# SHT4x_2.net
KiCad netlist of a schematic drawn in EAGLE
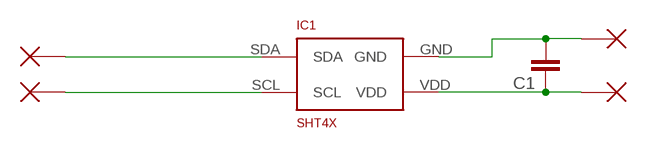
[diagram p0: schematic, sheet 1]

(export (version "E")
  (design (tool "Eeschema 10.0.6"))
  (components
    (comp (ref "C1")
      (value "SMD-C-1206")
      (footprint "eagle-import:C1206")
      (libsource (lib "eagle-import") (part "SMD-C-1206"))
    )
    (comp (ref "IC1")
      (value "SHT4X")
      (footprint "eagle-import:SHT4X")
      (libsource (lib "eagle-import") (part "SHT4X"))
    )
    (comp (ref "P1")
      (value "PIN")
      (footprint "eagle-import:PIN")
      (libsource (lib "eagle-import") (part "PIN"))
    )
    (comp (ref "P2")
      (value "PIN")
      (footprint "eagle-import:PIN")
      (libsource (lib "eagle-import") (part "PIN"))
    )
    (comp (ref "P3")
      (value "PIN")
      (footprint "eagle-import:PIN")
      (libsource (lib "eagle-import") (part "PIN"))
    )
    (comp (ref "P4")
      (value "PIN")
      (footprint "eagle-import:PIN")
      (libsource (lib "eagle-import") (part "PIN"))
    )
  )
  (nets
    (net (code "1") (name "Net-(C1-Pad1)") (class "Default")
      (node (ref "C1") (pin "1") (pinfunction "1_1") (pintype "passive"))
      (node (ref "IC1") (pin "VDD") (pinfunction "VDD_VDD") (pintype "bidirectional"))
      (node (ref "P4") (pin "P$1") (pinfunction "P$1_P$1") (pintype "bidirectional"))
    )
    (net (code "2") (name "Net-(C1-Pad2)") (class "Default")
      (node (ref "C1") (pin "2") (pinfunction "2_2") (pintype "passive"))
      (node (ref "IC1") (pin "GND") (pinfunction "GND_GND") (pintype "bidirectional"))
      (node (ref "P3") (pin "P$1") (pinfunction "P$1_P$1") (pintype "bidirectional"))
    )
    (net (code "3") (name "Net-(IC1-PadSCL)") (class "Default")
      (node (ref "IC1") (pin "SCL") (pinfunction "SCL_SCL") (pintype "bidirectional"))
      (node (ref "P2") (pin "P$1") (pinfunction "P$1_P$1") (pintype "bidirectional"))
    )
    (net (code "4") (name "Net-(IC1-PadSDA)") (class "Default")
      (node (ref "IC1") (pin "SDA") (pinfunction "SDA_SDA") (pintype "bidirectional"))
      (node (ref "P1") (pin "P$1") (pinfunction "P$1_P$1") (pintype "bidirectional"))
    )
  )
)
